# AUTOMATIC_LIGHTS_V2.net
KiCad netlist of a schematic drawn in EAGLE
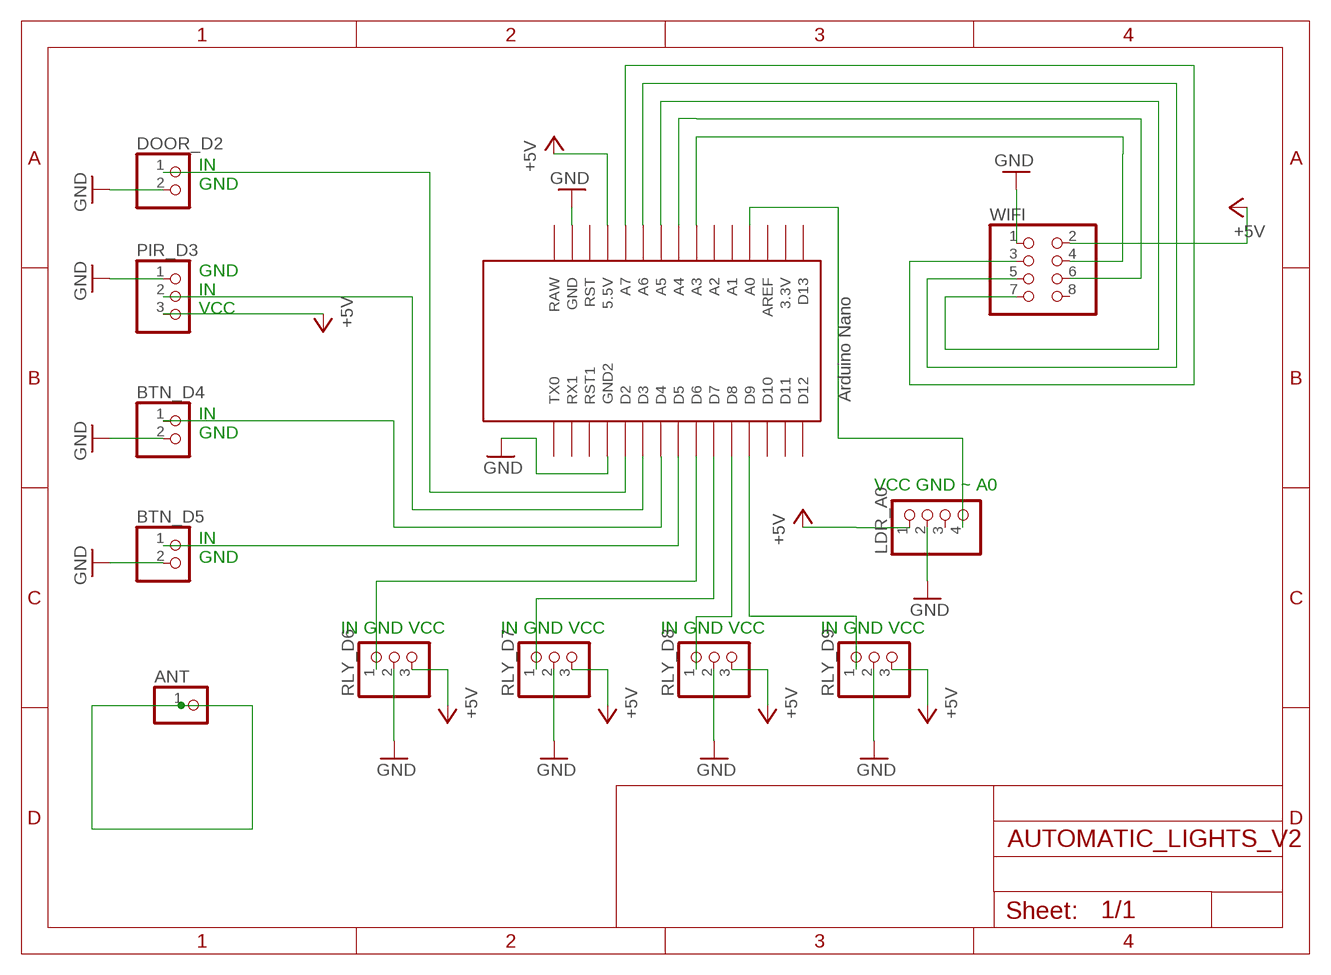
[diagram p0: schematic, sheet 1]

(export (version "E")
  (design (tool "Eeschema 10.0.6"))
  (components
    (comp (ref "ANT")
      (value "PINHD-1X1")
      (footprint "eagle-import:1X01")
      (libsource (lib "eagle-import") (part "PINHD-1X1"))
    )
    (comp (ref "BTN_D4")
      (value "PINHD-1X2")
      (footprint "eagle-import:1X02")
      (libsource (lib "eagle-import") (part "PINHD-1X2"))
    )
    (comp (ref "BTN_D5")
      (value "PINHD-1X2")
      (footprint "eagle-import:1X02")
      (libsource (lib "eagle-import") (part "PINHD-1X2"))
    )
    (comp (ref "DOOR_D2")
      (value "PINHD-1X2")
      (footprint "eagle-import:1X02")
      (libsource (lib "eagle-import") (part "PINHD-1X2"))
    )
    (comp (ref "LDR_A0")
      (value "PINHD-1X4")
      (footprint "eagle-import:1X04")
      (libsource (lib "eagle-import") (part "PINHD-1X4"))
    )
    (comp (ref "PIR_D3")
      (value "PINHD-1X3")
      (footprint "eagle-import:1X03")
      (libsource (lib "eagle-import") (part "PINHD-1X3"))
    )
    (comp (ref "RLY_D6")
      (value "PINHD-1X3")
      (footprint "eagle-import:1X03")
      (libsource (lib "eagle-import") (part "PINHD-1X3"))
    )
    (comp (ref "RLY_D7")
      (value "PINHD-1X3")
      (footprint "eagle-import:1X03")
      (libsource (lib "eagle-import") (part "PINHD-1X3"))
    )
    (comp (ref "RLY_D8")
      (value "PINHD-1X3")
      (footprint "eagle-import:1X03")
      (libsource (lib "eagle-import") (part "PINHD-1X3"))
    )
    (comp (ref "RLY_D9")
      (value "PINHD-1X3")
      (footprint "eagle-import:1X03")
      (libsource (lib "eagle-import") (part "PINHD-1X3"))
    )
    (comp (ref "U$1")
      (value "NANO")
      (footprint "eagle-import:NANO")
      (libsource (lib "eagle-import") (part "NANO"))
    )
    (comp (ref "WIFI")
      (value "PINHD-2X4")
      (footprint "eagle-import:2X04")
      (libsource (lib "eagle-import") (part "PINHD-2X4"))
    )
  )
  (nets
    (net (code "1") (name "+5V") (class "Default")
      (node (ref "LDR_A0") (pin "1") (pinfunction "1_1") (pintype "passive"))
      (node (ref "PIR_D3") (pin "3") (pinfunction "3_3") (pintype "passive"))
      (node (ref "RLY_D6") (pin "3") (pinfunction "3_3") (pintype "passive"))
      (node (ref "RLY_D7") (pin "3") (pinfunction "3_3") (pintype "passive"))
      (node (ref "RLY_D8") (pin "3") (pinfunction "3_3") (pintype "passive"))
      (node (ref "RLY_D9") (pin "3") (pinfunction "3_3") (pintype "passive"))
      (node (ref "U$1") (pin "5V") (pinfunction "5.5V_5V") (pintype "bidirectional"))
      (node (ref "WIFI") (pin "2") (pinfunction "2_2") (pintype "passive"))
    )
    (net (code "2") (name "GND") (class "Default")
      (node (ref "BTN_D4") (pin "2") (pinfunction "2_2") (pintype "passive"))
      (node (ref "BTN_D5") (pin "2") (pinfunction "2_2") (pintype "passive"))
      (node (ref "DOOR_D2") (pin "2") (pinfunction "2_2") (pintype "passive"))
      (node (ref "LDR_A0") (pin "2") (pinfunction "2_2") (pintype "passive"))
      (node (ref "PIR_D3") (pin "1") (pinfunction "1_1") (pintype "passive"))
      (node (ref "RLY_D6") (pin "2") (pinfunction "2_2") (pintype "passive"))
      (node (ref "RLY_D7") (pin "2") (pinfunction "2_2") (pintype "passive"))
      (node (ref "RLY_D8") (pin "2") (pinfunction "2_2") (pintype "passive"))
      (node (ref "RLY_D9") (pin "2") (pinfunction "2_2") (pintype "passive"))
      (node (ref "U$1") (pin "GND") (pinfunction "GND_GND") (pintype "bidirectional"))
      (node (ref "U$1") (pin "GND1") (pinfunction "GND2_GND1") (pintype "bidirectional"))
      (node (ref "WIFI") (pin "1") (pinfunction "1_1") (pintype "passive"))
    )
    (net (code "3") (name "Net-(BTN_D4-Pad1)") (class "Default")
      (node (ref "BTN_D4") (pin "1") (pinfunction "1_1") (pintype "passive"))
      (node (ref "U$1") (pin "D4") (pinfunction "D4_D4") (pintype "bidirectional"))
    )
    (net (code "4") (name "Net-(BTN_D5-Pad1)") (class "Default")
      (node (ref "BTN_D5") (pin "1") (pinfunction "1_1") (pintype "passive"))
      (node (ref "U$1") (pin "D5") (pinfunction "D5_D5") (pintype "bidirectional"))
    )
    (net (code "5") (name "Net-(DOOR_D2-Pad1)") (class "Default")
      (node (ref "DOOR_D2") (pin "1") (pinfunction "1_1") (pintype "passive"))
      (node (ref "U$1") (pin "D2") (pinfunction "D2_D2") (pintype "bidirectional"))
    )
    (net (code "6") (name "Net-(LDR_A0-Pad4)") (class "Default")
      (node (ref "LDR_A0") (pin "4") (pinfunction "4_4") (pintype "passive"))
      (node (ref "U$1") (pin "A0") (pinfunction "A0_A0") (pintype "bidirectional"))
    )
    (net (code "7") (name "Net-(PIR_D3-Pad2)") (class "Default")
      (node (ref "PIR_D3") (pin "2") (pinfunction "2_2") (pintype "passive"))
      (node (ref "U$1") (pin "D3") (pinfunction "D3_D3") (pintype "bidirectional"))
    )
    (net (code "8") (name "Net-(RLY_D6-Pad1)") (class "Default")
      (node (ref "RLY_D6") (pin "1") (pinfunction "1_1") (pintype "passive"))
      (node (ref "U$1") (pin "D6") (pinfunction "D6_D6") (pintype "bidirectional"))
    )
    (net (code "9") (name "Net-(RLY_D7-Pad1)") (class "Default")
      (node (ref "RLY_D7") (pin "1") (pinfunction "1_1") (pintype "passive"))
      (node (ref "U$1") (pin "D7") (pinfunction "D7_D7") (pintype "bidirectional"))
    )
    (net (code "10") (name "Net-(RLY_D8-Pad1)") (class "Default")
      (node (ref "RLY_D8") (pin "1") (pinfunction "1_1") (pintype "passive"))
      (node (ref "U$1") (pin "D8") (pinfunction "D8_D8") (pintype "bidirectional"))
    )
    (net (code "11") (name "Net-(RLY_D9-Pad1)") (class "Default")
      (node (ref "RLY_D9") (pin "1") (pinfunction "1_1") (pintype "passive"))
      (node (ref "U$1") (pin "D9") (pinfunction "D9_D9") (pintype "bidirectional"))
    )
    (net (code "12") (name "Net-(U$1-PadA3)") (class "Default")
      (node (ref "U$1") (pin "A3") (pinfunction "A3_A3") (pintype "bidirectional"))
      (node (ref "WIFI") (pin "4") (pinfunction "4_4") (pintype "passive"))
    )
    (net (code "13") (name "Net-(U$1-PadA4)") (class "Default")
      (node (ref "U$1") (pin "A4") (pinfunction "A4_A4") (pintype "bidirectional"))
      (node (ref "WIFI") (pin "6") (pinfunction "6_6") (pintype "passive"))
    )
    (net (code "14") (name "Net-(U$1-PadA5)") (class "Default")
      (node (ref "U$1") (pin "A5") (pinfunction "A5_A5") (pintype "bidirectional"))
      (node (ref "WIFI") (pin "7") (pinfunction "7_7") (pintype "passive"))
    )
    (net (code "15") (name "Net-(U$1-PadA6)") (class "Default")
      (node (ref "U$1") (pin "A6") (pinfunction "A6_A6") (pintype "bidirectional"))
      (node (ref "WIFI") (pin "5") (pinfunction "5_5") (pintype "passive"))
    )
    (net (code "16") (name "Net-(U$1-PadA7)") (class "Default")
      (node (ref "U$1") (pin "A7") (pinfunction "A7_A7") (pintype "bidirectional"))
      (node (ref "WIFI") (pin "3") (pinfunction "3_3") (pintype "passive"))
    )
    (net (code "17") (name "unconnected-(ANT-Pad1)") (class "Default")
      (node (ref "ANT") (pin "1") (pinfunction "1_1") (pintype "passive"))
    )
    (net (code "18") (name "unconnected-(LDR_A0-Pad3)") (class "Default")
      (node (ref "LDR_A0") (pin "3") (pinfunction "3_3") (pintype "passive"))
    )
    (net (code "19") (name "unconnected-(U$1-Pad3.3V)") (class "Default")
      (node (ref "U$1") (pin "3.3V") (pinfunction "3.3V_3.3V") (pintype "bidirectional"))
    )
    (net (code "20") (name "unconnected-(U$1-PadA1)") (class "Default")
      (node (ref "U$1") (pin "A1") (pinfunction "A1_A1") (pintype "bidirectional"))
    )
    (net (code "21") (name "unconnected-(U$1-PadA2)") (class "Default")
      (node (ref "U$1") (pin "A2") (pinfunction "A2_A2") (pintype "bidirectional"))
    )
    (net (code "22") (name "unconnected-(U$1-PadAREF)") (class "Default")
      (node (ref "U$1") (pin "AREF") (pinfunction "AREF_AREF") (pintype "bidirectional"))
    )
    (net (code "23") (name "unconnected-(U$1-PadD10)") (class "Default")
      (node (ref "U$1") (pin "D10") (pinfunction "D10_D10") (pintype "bidirectional"))
    )
    (net (code "24") (name "unconnected-(U$1-PadD11)") (class "Default")
      (node (ref "U$1") (pin "D11") (pinfunction "D11_D11") (pintype "bidirectional"))
    )
    (net (code "25") (name "unconnected-(U$1-PadD12)") (class "Default")
      (node (ref "U$1") (pin "D12") (pinfunction "D12_D12") (pintype "bidirectional"))
    )
    (net (code "26") (name "unconnected-(U$1-PadD13)") (class "Default")
      (node (ref "U$1") (pin "D13") (pinfunction "D13_D13") (pintype "bidirectional"))
    )
    (net (code "27") (name "unconnected-(U$1-PadICSP1)") (class "Default")
      (node (ref "U$1") (pin "ICSP1") (pinfunction "ICSP1_ICSP1") (pintype "bidirectional"))
    )
    (net (code "28") (name "unconnected-(U$1-PadICSP2)") (class "Default")
      (node (ref "U$1") (pin "ICSP2") (pinfunction "ICSP2_ICSP2") (pintype "bidirectional"))
    )
    (net (code "29") (name "unconnected-(U$1-PadICSP3)") (class "Default")
      (node (ref "U$1") (pin "ICSP3") (pinfunction "ICSP3_ICSP3") (pintype "bidirectional"))
    )
    (net (code "30") (name "unconnected-(U$1-PadICSP4)") (class "Default")
      (node (ref "U$1") (pin "ICSP4") (pinfunction "ICSP4_ICSP4") (pintype "bidirectional"))
    )
    (net (code "31") (name "unconnected-(U$1-PadICSP5)") (class "Default")
      (node (ref "U$1") (pin "ICSP5") (pinfunction "ICSP5_ICSP5") (pintype "bidirectional"))
    )
    (net (code "32") (name "unconnected-(U$1-PadICSP6)") (class "Default")
      (node (ref "U$1") (pin "ICSP6") (pinfunction "ICSP6_ICSP6") (pintype "bidirectional"))
    )
    (net (code "33") (name "unconnected-(U$1-PadRAW)") (class "Default")
      (node (ref "U$1") (pin "RAW") (pinfunction "RAW_RAW") (pintype "bidirectional"))
    )
    (net (code "34") (name "unconnected-(U$1-PadRST)") (class "Default")
      (node (ref "U$1") (pin "RST") (pinfunction "RST_RST") (pintype "bidirectional"))
    )
    (net (code "35") (name "unconnected-(U$1-PadRST1)") (class "Default")
      (node (ref "U$1") (pin "RST1") (pinfunction "RST1_RST1") (pintype "bidirectional"))
    )
    (net (code "36") (name "unconnected-(U$1-PadRX1)") (class "Default")
      (node (ref "U$1") (pin "RX1") (pinfunction "RX1_RX1") (pintype "bidirectional"))
    )
    (net (code "37") (name "unconnected-(U$1-PadTX0)") (class "Default")
      (node (ref "U$1") (pin "TX0") (pinfunction "TX0_TX0") (pintype "bidirectional"))
    )
    (net (code "38") (name "unconnected-(WIFI-Pad8)") (class "Default")
      (node (ref "WIFI") (pin "8") (pinfunction "8_8") (pintype "passive"))
    )
  )
)
